# 3_3V_LDO.net
KiCad netlist of a schematic drawn in Altium Designer
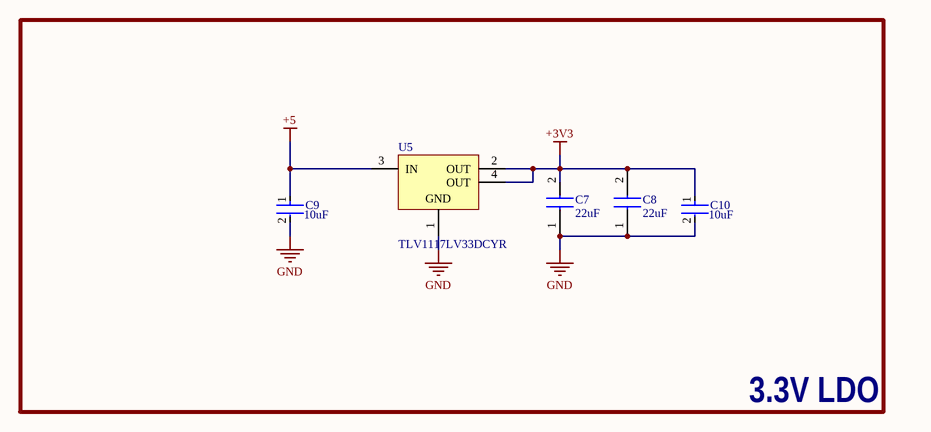
[diagram p0: 3.3V_LDO.SchDoc]

(export (version "E")
  (design (tool "Eeschema 10.0.6"))
  (components
    (comp (ref "C7")
      (value "22uF")
      (footprint "SamacSys:CAPC1608X105N")
      (description "Capacitor")
      (fields
        (field (name "MANUFACTURER_PART_NUMBER") "CL10A226MP8NUNE")
        (field (name "MOUSER PART NUMBER") "187-CL10A226MP8NUNE")
      )
      (libsource (lib "*") (part "CL10A226MP8NUNE"))
    )
    (comp (ref "C8")
      (value "22uF")
      (footprint "SamacSys:CAPC1608X105N")
      (description "Capacitor")
      (fields
        (field (name "MANUFACTURER_PART_NUMBER") "CL10A226MP8NUNE")
        (field (name "MOUSER PART NUMBER") "187-CL10A226MP8NUNE")
      )
      (libsource (lib "*") (part "CL10A226MP8NUNE"))
    )
    (comp (ref "C9")
      (value "CL05A106MP5NUNC")
      (footprint "FP-CL05A106MP5NUNC-MFG")
      (description "CAP CER 10UF 10V X5R 0402")
      (fields
        (field (name "OCTOPART") "https://octopart.com/cl05a106mp5nunc-samsung-22457395")
        (field (name "TOLERANCE") "20%")
        (field (name "CAPACITANCE") "10uF")
      )
      (libsource (lib "Altium Content Vault") (part "b4654b650e69147ec39a6b967a45e02"))
    )
    (comp (ref "C10")
      (value "CL05A106MP5NUNC")
      (footprint "FP-CL05A106MP5NUNC-MFG")
      (description "CAP CER 10UF 10V X5R 0402")
      (fields
        (field (name "OCTOPART") "https://octopart.com/cl05a106mp5nunc-samsung-22457395")
        (field (name "TOLERANCE") "20%")
        (field (name "CAPACITANCE") "10uF")
      )
      (libsource (lib "Altium Content Vault") (part "b4654b650e69147ec39a6b967a45e02"))
    )
    (comp (ref "U5")
      (value "TLV1117LV33DCYR")
      (footprint "DCY0004A_N")
      (fields (field (name "MANUFACTURER") "Texas Instruments"))
      (libsource (lib "Altium Content Vault") (part "TI-TLV1117LV33DCY4"))
    )
  )
  (nets
    (net (code "1") (name "+3V3") (class "Default")
      (node (ref "C10") (pin "1") (pinfunction "1_1") (pintype "passive"))
      (node (ref "C7") (pin "2") (pinfunction "2_2") (pintype "passive"))
      (node (ref "C8") (pin "2") (pinfunction "2_2") (pintype "passive"))
      (node (ref "U5") (pin "2") (pinfunction "OUT_2") (pintype "power_in"))
      (node (ref "U5") (pin "4") (pinfunction "OUT_4") (pintype "power_in"))
    )
    (net (code "2") (name "+5") (class "Default")
      (node (ref "C9") (pin "1") (pinfunction "1_1") (pintype "passive"))
      (node (ref "U5") (pin "3") (pinfunction "IN_3") (pintype "power_in"))
    )
    (net (code "3") (name "GND") (class "Default")
      (node (ref "C10") (pin "2") (pinfunction "2_2") (pintype "passive"))
      (node (ref "C7") (pin "1") (pinfunction "1_1") (pintype "passive"))
      (node (ref "C8") (pin "1") (pinfunction "1_1") (pintype "passive"))
      (node (ref "C9") (pin "2") (pinfunction "2_2") (pintype "passive"))
      (node (ref "U5") (pin "1") (pinfunction "GND_1") (pintype "power_in"))
    )
  )
)
